# 3_22.net
KiCad netlist of a schematic drawn in Altium Designer
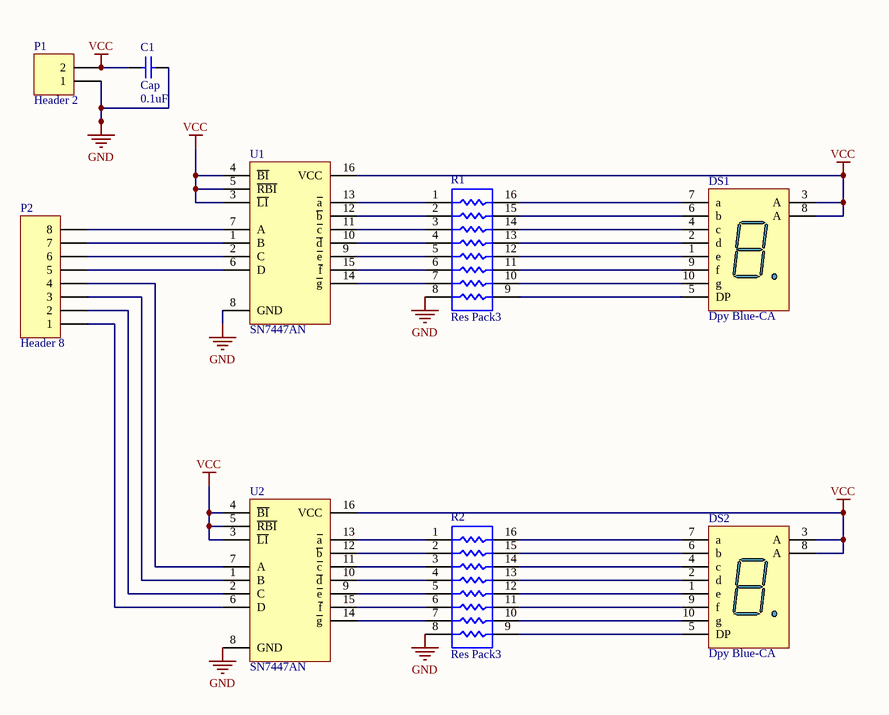
[diagram p0: 3.22.SchDoc]

(export (version "E")
  (design (tool "Eeschema 10.0.6"))
  (components
    (comp (ref "C1")
      (value "Cap")
      (footprint "RAD-0.3")
      (description "Capacitor")
      (fields (field (name "ALTIUM_VALUE") "0.1uF") (field (name "PUBLISHER") "Altium Limited"))
      (libsource (lib "Chap4-实践题(2)") (part "Cap"))
    )
    (comp (ref "DS1")
      (value "Dpy Blue-CA")
      (footprint "LEDDIP-10/C15.24RHD")
      (description "14.2 mm General Purpose Blue 7-Segment Display: CA, RH DP, Gray Surface")
      (fields (field (name "PUBLISHER") "Altium Limited"))
      (libsource (lib "Chap4-实践题(2)") (part "Dpy Blue-CA"))
    )
    (comp (ref "DS2")
      (value "Dpy Blue-CA")
      (footprint "LEDDIP-10/C15.24RHD")
      (description "14.2 mm General Purpose Blue 7-Segment Display: CA, RH DP, Gray Surface")
      (fields (field (name "PUBLISHER") "Altium Limited"))
      (libsource (lib "Chap4-实践题(2)") (part "Dpy Blue-CA"))
    )
    (comp (ref "P1")
      (value "Header 2")
      (footprint "HDR1X2")
      (description "Header, 2-Pin")
      (fields (field (name "PUBLISHER") "Altium Limited"))
      (libsource (lib "Chap4-实践题(2)") (part "Header 2"))
    )
    (comp (ref "P2")
      (value "Header 8")
      (footprint "HDR1X8")
      (description "Header, 8-Pin")
      (fields (field (name "PUBLISHER") "Altium Limited"))
      (libsource (lib "Chap4-实践题(2)") (part "Header 8"))
    )
    (comp (ref "R1")
      (value "Res Pack3")
      (footprint "SOIC127P600-16N")
      (description "Isolated Resistor Network")
      (fields (field (name "PUBLISHER") "Altium Limited"))
      (libsource (lib "Chap4-实践题(2)") (part "Res Pack3"))
    )
    (comp (ref "R2")
      (value "Res Pack3")
      (footprint "SOIC127P600-16N")
      (description "Isolated Resistor Network")
      (fields (field (name "PUBLISHER") "Altium Limited"))
      (libsource (lib "Chap4-实践题(2)") (part "Res Pack3"))
    )
    (comp (ref "U1")
      (value "SN7447AN")
      (footprint "PCBComponent_1")
      (libsource (lib "Chap4-实践题(2)") (part "SN7447"))
    )
    (comp (ref "U2")
      (value "SN7447AN")
      (footprint "PCBComponent_1")
      (libsource (lib "Chap4-实践题(2)") (part "SN7447"))
    )
  )
  (nets
    (net (code "1") (name "GND") (class "Default")
      (node (ref "C1") (pin "2") (pinfunction "2_2") (pintype "passive"))
      (node (ref "P1") (pin "1") (pinfunction "1_1") (pintype "passive"))
      (node (ref "R1") (pin "8") (pinfunction "8_8") (pintype "passive"))
      (node (ref "R2") (pin "8") (pinfunction "8_8") (pintype "passive"))
      (node (ref "U1") (pin "8") (pinfunction "GND_8") (pintype "passive"))
      (node (ref "U2") (pin "8") (pinfunction "GND_8") (pintype "passive"))
    )
    (net (code "2") (name "Net-(DS1-DP)") (class "Default")
      (node (ref "DS1") (pin "5") (pinfunction "DP_5") (pintype "passive"))
      (node (ref "R1") (pin "9") (pinfunction "9_9") (pintype "passive"))
    )
    (net (code "3") (name "Net-(DS1-a)") (class "Default")
      (node (ref "DS1") (pin "7") (pinfunction "a_7") (pintype "passive"))
      (node (ref "R1") (pin "16") (pinfunction "16_16") (pintype "passive"))
    )
    (net (code "4") (name "Net-(DS1-b)") (class "Default")
      (node (ref "DS1") (pin "6") (pinfunction "b_6") (pintype "passive"))
      (node (ref "R1") (pin "15") (pinfunction "15_15") (pintype "passive"))
    )
    (net (code "5") (name "Net-(DS1-c)") (class "Default")
      (node (ref "DS1") (pin "4") (pinfunction "c_4") (pintype "passive"))
      (node (ref "R1") (pin "14") (pinfunction "14_14") (pintype "passive"))
    )
    (net (code "6") (name "Net-(DS1-d)") (class "Default")
      (node (ref "DS1") (pin "2") (pinfunction "d_2") (pintype "passive"))
      (node (ref "R1") (pin "13") (pinfunction "13_13") (pintype "passive"))
    )
    (net (code "7") (name "Net-(DS1-e)") (class "Default")
      (node (ref "DS1") (pin "1") (pinfunction "e_1") (pintype "passive"))
      (node (ref "R1") (pin "12") (pinfunction "12_12") (pintype "passive"))
    )
    (net (code "8") (name "Net-(DS1-f)") (class "Default")
      (node (ref "DS1") (pin "9") (pinfunction "f_9") (pintype "passive"))
      (node (ref "R1") (pin "11") (pinfunction "11_11") (pintype "passive"))
    )
    (net (code "9") (name "Net-(DS1-g)") (class "Default")
      (node (ref "DS1") (pin "10") (pinfunction "g_10") (pintype "passive"))
      (node (ref "R1") (pin "10") (pinfunction "10_10") (pintype "passive"))
    )
    (net (code "10") (name "Net-(DS2-DP)") (class "Default")
      (node (ref "DS2") (pin "5") (pinfunction "DP_5") (pintype "passive"))
      (node (ref "R2") (pin "9") (pinfunction "9_9") (pintype "passive"))
    )
    (net (code "11") (name "Net-(DS2-a)") (class "Default")
      (node (ref "DS2") (pin "7") (pinfunction "a_7") (pintype "passive"))
      (node (ref "R2") (pin "16") (pinfunction "16_16") (pintype "passive"))
    )
    (net (code "12") (name "Net-(DS2-b)") (class "Default")
      (node (ref "DS2") (pin "6") (pinfunction "b_6") (pintype "passive"))
      (node (ref "R2") (pin "15") (pinfunction "15_15") (pintype "passive"))
    )
    (net (code "13") (name "Net-(DS2-c)") (class "Default")
      (node (ref "DS2") (pin "4") (pinfunction "c_4") (pintype "passive"))
      (node (ref "R2") (pin "14") (pinfunction "14_14") (pintype "passive"))
    )
    (net (code "14") (name "Net-(DS2-d)") (class "Default")
      (node (ref "DS2") (pin "2") (pinfunction "d_2") (pintype "passive"))
      (node (ref "R2") (pin "13") (pinfunction "13_13") (pintype "passive"))
    )
    (net (code "15") (name "Net-(DS2-e)") (class "Default")
      (node (ref "DS2") (pin "1") (pinfunction "e_1") (pintype "passive"))
      (node (ref "R2") (pin "12") (pinfunction "12_12") (pintype "passive"))
    )
    (net (code "16") (name "Net-(DS2-f)") (class "Default")
      (node (ref "DS2") (pin "9") (pinfunction "f_9") (pintype "passive"))
      (node (ref "R2") (pin "11") (pinfunction "11_11") (pintype "passive"))
    )
    (net (code "17") (name "Net-(DS2-g)") (class "Default")
      (node (ref "DS2") (pin "10") (pinfunction "g_10") (pintype "passive"))
      (node (ref "R2") (pin "10") (pinfunction "10_10") (pintype "passive"))
    )
    (net (code "18") (name "Net-(U1-A)") (class "Default")
      (node (ref "P2") (pin "8") (pinfunction "8_8") (pintype "passive"))
      (node (ref "U1") (pin "7") (pinfunction "A_7") (pintype "passive"))
    )
    (net (code "19") (name "Net-(U1-B)") (class "Default")
      (node (ref "P2") (pin "7") (pinfunction "7_7") (pintype "passive"))
      (node (ref "U1") (pin "1") (pinfunction "B_1") (pintype "passive"))
    )
    (net (code "20") (name "Net-(U1-C)") (class "Default")
      (node (ref "P2") (pin "6") (pinfunction "6_6") (pintype "passive"))
      (node (ref "U1") (pin "2") (pinfunction "C_2") (pintype "passive"))
    )
    (net (code "21") (name "Net-(U1-D)") (class "Default")
      (node (ref "P2") (pin "5") (pinfunction "5_5") (pintype "passive"))
      (node (ref "U1") (pin "6") (pinfunction "D_6") (pintype "passive"))
    )
    (net (code "22") (name "Net-(U1-~{a})") (class "Default")
      (node (ref "R1") (pin "1") (pinfunction "1_1") (pintype "passive"))
      (node (ref "U1") (pin "13") (pinfunction "~{a}_13") (pintype "passive"))
    )
    (net (code "23") (name "Net-(U1-~{b})") (class "Default")
      (node (ref "R1") (pin "2") (pinfunction "2_2") (pintype "passive"))
      (node (ref "U1") (pin "12") (pinfunction "~{b}_12") (pintype "passive"))
    )
    (net (code "24") (name "Net-(U1-~{c})") (class "Default")
      (node (ref "R1") (pin "3") (pinfunction "3_3") (pintype "passive"))
      (node (ref "U1") (pin "11") (pinfunction "~{c}_11") (pintype "passive"))
    )
    (net (code "25") (name "Net-(U1-~{d})") (class "Default")
      (node (ref "R1") (pin "4") (pinfunction "4_4") (pintype "passive"))
      (node (ref "U1") (pin "10") (pinfunction "~{d}_10") (pintype "passive"))
    )
    (net (code "26") (name "Net-(U1-~{e})") (class "Default")
      (node (ref "R1") (pin "5") (pinfunction "5_5") (pintype "passive"))
      (node (ref "U1") (pin "9") (pinfunction "~{e}_9") (pintype "passive"))
    )
    (net (code "27") (name "Net-(U1-~{f})") (class "Default")
      (node (ref "R1") (pin "6") (pinfunction "6_6") (pintype "passive"))
      (node (ref "U1") (pin "15") (pinfunction "~{f}_15") (pintype "passive"))
    )
    (net (code "28") (name "Net-(U1-~{g})") (class "Default")
      (node (ref "R1") (pin "7") (pinfunction "7_7") (pintype "passive"))
      (node (ref "U1") (pin "14") (pinfunction "~{g}_14") (pintype "passive"))
    )
    (net (code "29") (name "Net-(U2-A)") (class "Default")
      (node (ref "P2") (pin "4") (pinfunction "4_4") (pintype "passive"))
      (node (ref "U2") (pin "7") (pinfunction "A_7") (pintype "passive"))
    )
    (net (code "30") (name "Net-(U2-B)") (class "Default")
      (node (ref "P2") (pin "3") (pinfunction "3_3") (pintype "passive"))
      (node (ref "U2") (pin "1") (pinfunction "B_1") (pintype "passive"))
    )
    (net (code "31") (name "Net-(U2-C)") (class "Default")
      (node (ref "P2") (pin "2") (pinfunction "2_2") (pintype "passive"))
      (node (ref "U2") (pin "2") (pinfunction "C_2") (pintype "passive"))
    )
    (net (code "32") (name "Net-(U2-D)") (class "Default")
      (node (ref "P2") (pin "1") (pinfunction "1_1") (pintype "passive"))
      (node (ref "U2") (pin "6") (pinfunction "D_6") (pintype "passive"))
    )
    (net (code "33") (name "Net-(U2-~{a})") (class "Default")
      (node (ref "R2") (pin "1") (pinfunction "1_1") (pintype "passive"))
      (node (ref "U2") (pin "13") (pinfunction "~{a}_13") (pintype "passive"))
    )
    (net (code "34") (name "Net-(U2-~{b})") (class "Default")
      (node (ref "R2") (pin "2") (pinfunction "2_2") (pintype "passive"))
      (node (ref "U2") (pin "12") (pinfunction "~{b}_12") (pintype "passive"))
    )
    (net (code "35") (name "Net-(U2-~{c})") (class "Default")
      (node (ref "R2") (pin "3") (pinfunction "3_3") (pintype "passive"))
      (node (ref "U2") (pin "11") (pinfunction "~{c}_11") (pintype "passive"))
    )
    (net (code "36") (name "Net-(U2-~{d})") (class "Default")
      (node (ref "R2") (pin "4") (pinfunction "4_4") (pintype "passive"))
      (node (ref "U2") (pin "10") (pinfunction "~{d}_10") (pintype "passive"))
    )
    (net (code "37") (name "Net-(U2-~{e})") (class "Default")
      (node (ref "R2") (pin "5") (pinfunction "5_5") (pintype "passive"))
      (node (ref "U2") (pin "9") (pinfunction "~{e}_9") (pintype "passive"))
    )
    (net (code "38") (name "Net-(U2-~{f})") (class "Default")
      (node (ref "R2") (pin "6") (pinfunction "6_6") (pintype "passive"))
      (node (ref "U2") (pin "15") (pinfunction "~{f}_15") (pintype "passive"))
    )
    (net (code "39") (name "Net-(U2-~{g})") (class "Default")
      (node (ref "R2") (pin "7") (pinfunction "7_7") (pintype "passive"))
      (node (ref "U2") (pin "14") (pinfunction "~{g}_14") (pintype "passive"))
    )
    (net (code "40") (name "VCC") (class "Default")
      (node (ref "C1") (pin "1") (pinfunction "1_1") (pintype "passive"))
      (node (ref "DS1") (pin "3") (pinfunction "A_3") (pintype "passive"))
      (node (ref "DS1") (pin "8") (pinfunction "A_8") (pintype "passive"))
      (node (ref "DS2") (pin "3") (pinfunction "A_3") (pintype "passive"))
      (node (ref "DS2") (pin "8") (pinfunction "A_8") (pintype "passive"))
      (node (ref "P1") (pin "2") (pinfunction "2_2") (pintype "passive"))
      (node (ref "U1") (pin "16") (pinfunction "VCC_16") (pintype "passive"))
      (node (ref "U1") (pin "3") (pinfunction "~{LI}_3") (pintype "passive"))
      (node (ref "U1") (pin "4") (pinfunction "~{BI}_4") (pintype "passive"))
      (node (ref "U1") (pin "5") (pinfunction "~{RBI}_5") (pintype "passive"))
      (node (ref "U2") (pin "16") (pinfunction "VCC_16") (pintype "passive"))
      (node (ref "U2") (pin "3") (pinfunction "~{LI}_3") (pintype "passive"))
      (node (ref "U2") (pin "4") (pinfunction "~{BI}_4") (pintype "passive"))
      (node (ref "U2") (pin "5") (pinfunction "~{RBI}_5") (pintype "passive"))
    )
  )
)
